# voltage_multiplier_v10.net
KiCad netlist of a schematic drawn in EAGLE
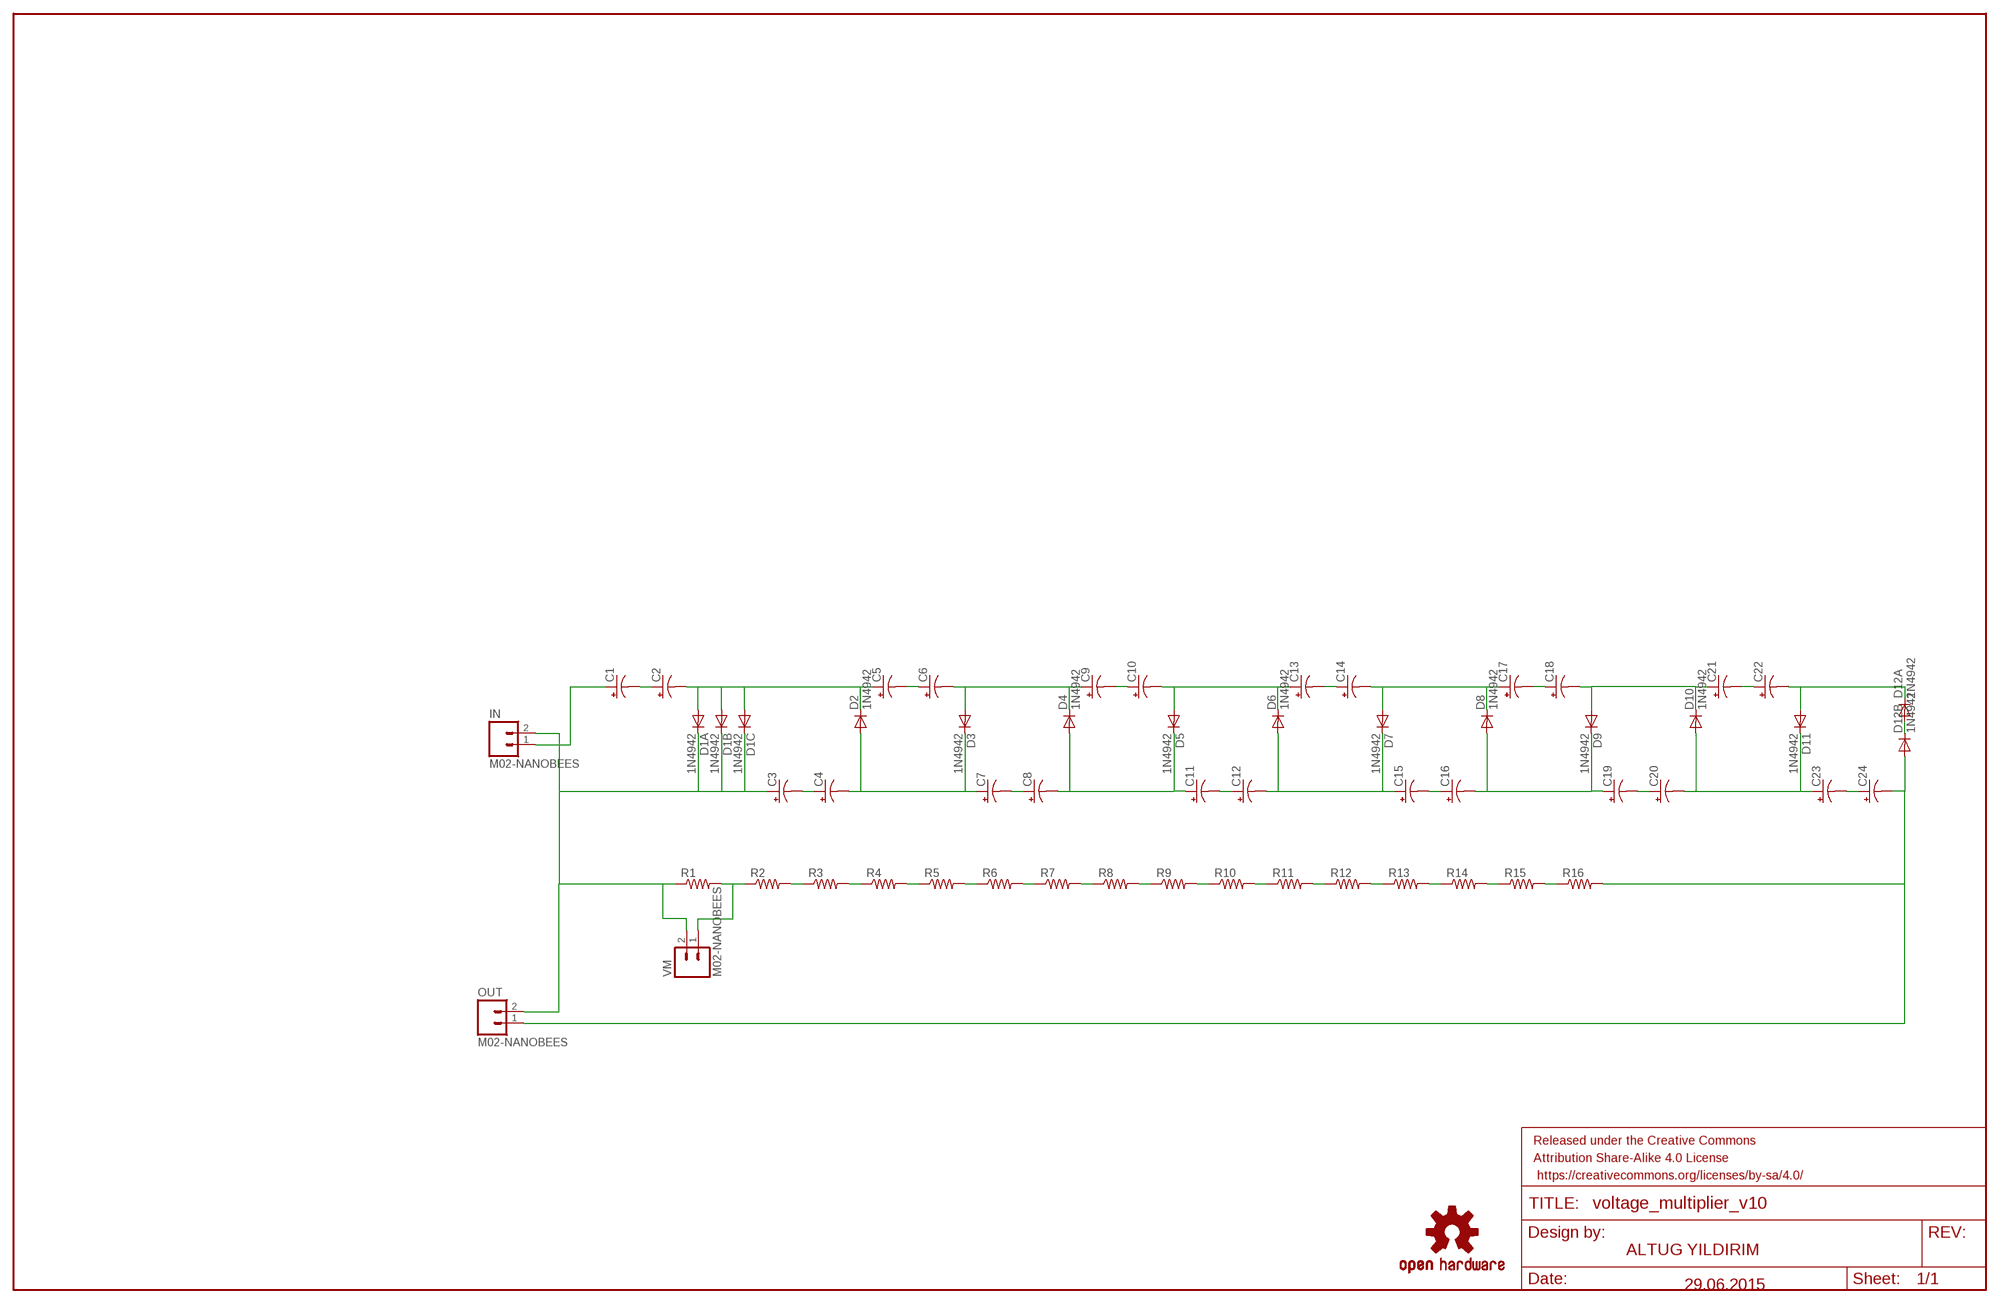
[diagram p0: schematic, sheet 1]

(export (version "E")
  (design (tool "Eeschema 10.0.6"))
  (components
    (comp (ref "C1")
      (value "CAP_POLPTH3")
      (footprint "eagle-import:CPOL-RADIAL-1000UF-63V")
      (libsource (lib "eagle-import") (part "CAP_POLPTH3"))
    )
    (comp (ref "C2")
      (value "CAP_POLPTH3")
      (footprint "eagle-import:CPOL-RADIAL-1000UF-63V")
      (libsource (lib "eagle-import") (part "CAP_POLPTH3"))
    )
    (comp (ref "C3")
      (value "CAP_POLPTH3")
      (footprint "eagle-import:CPOL-RADIAL-1000UF-63V")
      (libsource (lib "eagle-import") (part "CAP_POLPTH3"))
    )
    (comp (ref "C4")
      (value "CAP_POLPTH3")
      (footprint "eagle-import:CPOL-RADIAL-1000UF-63V")
      (libsource (lib "eagle-import") (part "CAP_POLPTH3"))
    )
    (comp (ref "C5")
      (value "CAP_POLPTH3")
      (footprint "eagle-import:CPOL-RADIAL-1000UF-63V")
      (libsource (lib "eagle-import") (part "CAP_POLPTH3"))
    )
    (comp (ref "C6")
      (value "CAP_POLPTH3")
      (footprint "eagle-import:CPOL-RADIAL-1000UF-63V")
      (libsource (lib "eagle-import") (part "CAP_POLPTH3"))
    )
    (comp (ref "C7")
      (value "CAP_POLPTH3")
      (footprint "eagle-import:CPOL-RADIAL-1000UF-63V")
      (libsource (lib "eagle-import") (part "CAP_POLPTH3"))
    )
    (comp (ref "C8")
      (value "CAP_POLPTH3")
      (footprint "eagle-import:CPOL-RADIAL-1000UF-63V")
      (libsource (lib "eagle-import") (part "CAP_POLPTH3"))
    )
    (comp (ref "C9")
      (value "CAP_POLPTH3")
      (footprint "eagle-import:CPOL-RADIAL-1000UF-63V")
      (libsource (lib "eagle-import") (part "CAP_POLPTH3"))
    )
    (comp (ref "C10")
      (value "CAP_POLPTH3")
      (footprint "eagle-import:CPOL-RADIAL-1000UF-63V")
      (libsource (lib "eagle-import") (part "CAP_POLPTH3"))
    )
    (comp (ref "C11")
      (value "CAP_POLPTH3")
      (footprint "eagle-import:CPOL-RADIAL-1000UF-63V")
      (libsource (lib "eagle-import") (part "CAP_POLPTH3"))
    )
    (comp (ref "C12")
      (value "CAP_POLPTH3")
      (footprint "eagle-import:CPOL-RADIAL-1000UF-63V")
      (libsource (lib "eagle-import") (part "CAP_POLPTH3"))
    )
    (comp (ref "C13")
      (value "CAP_POLPTH3")
      (footprint "eagle-import:CPOL-RADIAL-1000UF-63V")
      (libsource (lib "eagle-import") (part "CAP_POLPTH3"))
    )
    (comp (ref "C14")
      (value "CAP_POLPTH3")
      (footprint "eagle-import:CPOL-RADIAL-1000UF-63V")
      (libsource (lib "eagle-import") (part "CAP_POLPTH3"))
    )
    (comp (ref "C15")
      (value "CAP_POLPTH3")
      (footprint "eagle-import:CPOL-RADIAL-1000UF-63V")
      (libsource (lib "eagle-import") (part "CAP_POLPTH3"))
    )
    (comp (ref "C16")
      (value "CAP_POLPTH3")
      (footprint "eagle-import:CPOL-RADIAL-1000UF-63V")
      (libsource (lib "eagle-import") (part "CAP_POLPTH3"))
    )
    (comp (ref "C17")
      (value "CAP_POLPTH3")
      (footprint "eagle-import:CPOL-RADIAL-1000UF-63V")
      (libsource (lib "eagle-import") (part "CAP_POLPTH3"))
    )
    (comp (ref "C18")
      (value "CAP_POLPTH3")
      (footprint "eagle-import:CPOL-RADIAL-1000UF-63V")
      (libsource (lib "eagle-import") (part "CAP_POLPTH3"))
    )
    (comp (ref "C19")
      (value "CAP_POLPTH3")
      (footprint "eagle-import:CPOL-RADIAL-1000UF-63V")
      (libsource (lib "eagle-import") (part "CAP_POLPTH3"))
    )
    (comp (ref "C20")
      (value "CAP_POLPTH3")
      (footprint "eagle-import:CPOL-RADIAL-1000UF-63V")
      (libsource (lib "eagle-import") (part "CAP_POLPTH3"))
    )
    (comp (ref "C21")
      (value "CAP_POLPTH3")
      (footprint "eagle-import:CPOL-RADIAL-1000UF-63V")
      (libsource (lib "eagle-import") (part "CAP_POLPTH3"))
    )
    (comp (ref "C22")
      (value "CAP_POLPTH3")
      (footprint "eagle-import:CPOL-RADIAL-1000UF-63V")
      (libsource (lib "eagle-import") (part "CAP_POLPTH3"))
    )
    (comp (ref "C23")
      (value "CAP_POLPTH3")
      (footprint "eagle-import:CPOL-RADIAL-1000UF-63V")
      (libsource (lib "eagle-import") (part "CAP_POLPTH3"))
    )
    (comp (ref "C24")
      (value "CAP_POLPTH3")
      (footprint "eagle-import:CPOL-RADIAL-1000UF-63V")
      (libsource (lib "eagle-import") (part "CAP_POLPTH3"))
    )
    (comp (ref "D1A")
      (value "1N4942")
      (footprint "eagle-import:DO41-10")
      (libsource (lib "eagle-import") (part "1N4942"))
    )
    (comp (ref "D1B")
      (value "1N4942")
      (footprint "eagle-import:DO41-10")
      (libsource (lib "eagle-import") (part "1N4942"))
    )
    (comp (ref "D1C")
      (value "1N4942")
      (footprint "eagle-import:DO41-10")
      (libsource (lib "eagle-import") (part "1N4942"))
    )
    (comp (ref "D2")
      (value "1N4942")
      (footprint "eagle-import:DO41-10")
      (libsource (lib "eagle-import") (part "1N4942"))
    )
    (comp (ref "D3")
      (value "1N4942")
      (footprint "eagle-import:DO41-10")
      (libsource (lib "eagle-import") (part "1N4942"))
    )
    (comp (ref "D4")
      (value "1N4942")
      (footprint "eagle-import:DO41-10")
      (libsource (lib "eagle-import") (part "1N4942"))
    )
    (comp (ref "D5")
      (value "1N4942")
      (footprint "eagle-import:DO41-10")
      (libsource (lib "eagle-import") (part "1N4942"))
    )
    (comp (ref "D6")
      (value "1N4942")
      (footprint "eagle-import:DO41-10")
      (libsource (lib "eagle-import") (part "1N4942"))
    )
    (comp (ref "D7")
      (value "1N4942")
      (footprint "eagle-import:DO41-10")
      (libsource (lib "eagle-import") (part "1N4942"))
    )
    (comp (ref "D8")
      (value "1N4942")
      (footprint "eagle-import:DO41-10")
      (libsource (lib "eagle-import") (part "1N4942"))
    )
    (comp (ref "D9")
      (value "1N4942")
      (footprint "eagle-import:DO41-10")
      (libsource (lib "eagle-import") (part "1N4942"))
    )
    (comp (ref "D10")
      (value "1N4942")
      (footprint "eagle-import:DO41-10")
      (libsource (lib "eagle-import") (part "1N4942"))
    )
    (comp (ref "D11")
      (value "1N4942")
      (footprint "eagle-import:DO41-10")
      (libsource (lib "eagle-import") (part "1N4942"))
    )
    (comp (ref "D12A")
      (value "1N4942")
      (footprint "eagle-import:DO41-10")
      (libsource (lib "eagle-import") (part "1N4942"))
    )
    (comp (ref "D12B")
      (value "1N4942")
      (footprint "eagle-import:DO41-10")
      (libsource (lib "eagle-import") (part "1N4942"))
    )
    (comp (ref "FRAME1")
      (value "FRAME-LEDGER")
      (footprint "eagle-import:CREATIVE_COMMONS")
      (libsource (lib "eagle-import") (part "FRAME-LEDGER"))
    )
    (comp (ref "IN")
      (value "M02-NANOBEES")
      (footprint "eagle-import:M02-NANOBEES")
      (libsource (lib "eagle-import") (part "M02-NANOBEES"))
    )
    (comp (ref "LOGO1")
      (value "OSHW-LOGOM")
      (footprint "eagle-import:OSHW-LOGO-M")
      (libsource (lib "eagle-import") (part "OSHW-LOGOM"))
    )
    (comp (ref "OUT")
      (value "M02-NANOBEES")
      (footprint "eagle-import:M02-NANOBEES")
      (libsource (lib "eagle-import") (part "M02-NANOBEES"))
    )
    (comp (ref "R1")
      (value "RESISTORPTH-1/4W")
      (footprint "eagle-import:AXIAL-0.4")
      (libsource (lib "eagle-import") (part "RESISTORPTH-1/4W"))
    )
    (comp (ref "R2")
      (value "RESISTORPTH-1/4W")
      (footprint "eagle-import:AXIAL-0.4")
      (libsource (lib "eagle-import") (part "RESISTORPTH-1/4W"))
    )
    (comp (ref "R3")
      (value "RESISTORPTH-1/4W")
      (footprint "eagle-import:AXIAL-0.4")
      (libsource (lib "eagle-import") (part "RESISTORPTH-1/4W"))
    )
    (comp (ref "R4")
      (value "RESISTORPTH-1/4W")
      (footprint "eagle-import:AXIAL-0.4")
      (libsource (lib "eagle-import") (part "RESISTORPTH-1/4W"))
    )
    (comp (ref "R5")
      (value "RESISTORPTH-1/4W")
      (footprint "eagle-import:AXIAL-0.4")
      (libsource (lib "eagle-import") (part "RESISTORPTH-1/4W"))
    )
    (comp (ref "R6")
      (value "RESISTORPTH-1/4W")
      (footprint "eagle-import:AXIAL-0.4")
      (libsource (lib "eagle-import") (part "RESISTORPTH-1/4W"))
    )
    (comp (ref "R7")
      (value "RESISTORPTH-1/4W")
      (footprint "eagle-import:AXIAL-0.4")
      (libsource (lib "eagle-import") (part "RESISTORPTH-1/4W"))
    )
    (comp (ref "R8")
      (value "RESISTORPTH-1/4W")
      (footprint "eagle-import:AXIAL-0.4")
      (libsource (lib "eagle-import") (part "RESISTORPTH-1/4W"))
    )
    (comp (ref "R9")
      (value "RESISTORPTH-1/4W")
      (footprint "eagle-import:AXIAL-0.4")
      (libsource (lib "eagle-import") (part "RESISTORPTH-1/4W"))
    )
    (comp (ref "R10")
      (value "RESISTORPTH-1/4W")
      (footprint "eagle-import:AXIAL-0.4")
      (libsource (lib "eagle-import") (part "RESISTORPTH-1/4W"))
    )
    (comp (ref "R11")
      (value "RESISTORPTH-1/4W")
      (footprint "eagle-import:AXIAL-0.4")
      (libsource (lib "eagle-import") (part "RESISTORPTH-1/4W"))
    )
    (comp (ref "R12")
      (value "RESISTORPTH-1/4W")
      (footprint "eagle-import:AXIAL-0.4")
      (libsource (lib "eagle-import") (part "RESISTORPTH-1/4W"))
    )
    (comp (ref "R13")
      (value "RESISTORPTH-1/4W")
      (footprint "eagle-import:AXIAL-0.4")
      (libsource (lib "eagle-import") (part "RESISTORPTH-1/4W"))
    )
    (comp (ref "R14")
      (value "RESISTORPTH-1/4W")
      (footprint "eagle-import:AXIAL-0.4")
      (libsource (lib "eagle-import") (part "RESISTORPTH-1/4W"))
    )
    (comp (ref "R15")
      (value "RESISTORPTH-1/4W")
      (footprint "eagle-import:AXIAL-0.4")
      (libsource (lib "eagle-import") (part "RESISTORPTH-1/4W"))
    )
    (comp (ref "R16")
      (value "RESISTORPTH-1/4W")
      (footprint "eagle-import:AXIAL-0.4")
      (libsource (lib "eagle-import") (part "RESISTORPTH-1/4W"))
    )
    (comp (ref "VM")
      (value "M02-NANOBEES")
      (footprint "eagle-import:M02-NANOBEES")
      (libsource (lib "eagle-import") (part "M02-NANOBEES"))
    )
  )
  (nets
    (net (code "1") (name "Net-(C1-+)") (class "Default")
      (node (ref "C1") (pin "1") (pinfunction "+_1") (pintype "passive"))
      (node (ref "IN") (pin "1") (pinfunction "1_1") (pintype "passive"))
    )
    (net (code "2") (name "Net-(C1--)") (class "Default")
      (node (ref "C1") (pin "2") (pinfunction "-_2") (pintype "passive"))
      (node (ref "C2") (pin "1") (pinfunction "+_1") (pintype "passive"))
    )
    (net (code "3") (name "Net-(C2--)") (class "Default")
      (node (ref "C2") (pin "2") (pinfunction "-_2") (pintype "passive"))
      (node (ref "C5") (pin "1") (pinfunction "+_1") (pintype "passive"))
      (node (ref "D1A") (pin "A") (pinfunction "A_A") (pintype "passive"))
      (node (ref "D1B") (pin "A") (pinfunction "A_A") (pintype "passive"))
      (node (ref "D1C") (pin "A") (pinfunction "A_A") (pintype "passive"))
      (node (ref "D2") (pin "C") (pinfunction "C_C") (pintype "passive"))
    )
    (net (code "4") (name "Net-(C3-+)") (class "Default")
      (node (ref "C3") (pin "1") (pinfunction "+_1") (pintype "passive"))
      (node (ref "D1A") (pin "C") (pinfunction "C_C") (pintype "passive"))
      (node (ref "D1B") (pin "C") (pinfunction "C_C") (pintype "passive"))
      (node (ref "D1C") (pin "C") (pinfunction "C_C") (pintype "passive"))
      (node (ref "IN") (pin "2") (pinfunction "2_2") (pintype "passive"))
      (node (ref "OUT") (pin "2") (pinfunction "2_2") (pintype "passive"))
      (node (ref "R1") (pin "P$1") (pinfunction "1_P$1") (pintype "passive"))
      (node (ref "VM") (pin "2") (pinfunction "2_2") (pintype "passive"))
    )
    (net (code "5") (name "Net-(C3--)") (class "Default")
      (node (ref "C3") (pin "2") (pinfunction "-_2") (pintype "passive"))
      (node (ref "C4") (pin "1") (pinfunction "+_1") (pintype "passive"))
    )
    (net (code "6") (name "Net-(C4--)") (class "Default")
      (node (ref "C4") (pin "2") (pinfunction "-_2") (pintype "passive"))
      (node (ref "C7") (pin "1") (pinfunction "+_1") (pintype "passive"))
      (node (ref "D2") (pin "A") (pinfunction "A_A") (pintype "passive"))
      (node (ref "D3") (pin "C") (pinfunction "C_C") (pintype "passive"))
    )
    (net (code "7") (name "Net-(C5--)") (class "Default")
      (node (ref "C5") (pin "2") (pinfunction "-_2") (pintype "passive"))
      (node (ref "C6") (pin "1") (pinfunction "+_1") (pintype "passive"))
    )
    (net (code "8") (name "Net-(C6--)") (class "Default")
      (node (ref "C6") (pin "2") (pinfunction "-_2") (pintype "passive"))
      (node (ref "C9") (pin "1") (pinfunction "+_1") (pintype "passive"))
      (node (ref "D3") (pin "A") (pinfunction "A_A") (pintype "passive"))
      (node (ref "D4") (pin "C") (pinfunction "C_C") (pintype "passive"))
    )
    (net (code "9") (name "Net-(C7--)") (class "Default")
      (node (ref "C7") (pin "2") (pinfunction "-_2") (pintype "passive"))
      (node (ref "C8") (pin "1") (pinfunction "+_1") (pintype "passive"))
    )
    (net (code "10") (name "Net-(C10-+)") (class "Default")
      (node (ref "C10") (pin "1") (pinfunction "+_1") (pintype "passive"))
      (node (ref "C9") (pin "2") (pinfunction "-_2") (pintype "passive"))
    )
    (net (code "11") (name "Net-(C10--)") (class "Default")
      (node (ref "C10") (pin "2") (pinfunction "-_2") (pintype "passive"))
      (node (ref "C13") (pin "1") (pinfunction "+_1") (pintype "passive"))
      (node (ref "D5") (pin "A") (pinfunction "A_A") (pintype "passive"))
      (node (ref "D6") (pin "C") (pinfunction "C_C") (pintype "passive"))
    )
    (net (code "12") (name "Net-(C11-+)") (class "Default")
      (node (ref "C11") (pin "1") (pinfunction "+_1") (pintype "passive"))
      (node (ref "C8") (pin "2") (pinfunction "-_2") (pintype "passive"))
      (node (ref "D4") (pin "A") (pinfunction "A_A") (pintype "passive"))
      (node (ref "D5") (pin "C") (pinfunction "C_C") (pintype "passive"))
    )
    (net (code "13") (name "Net-(C11--)") (class "Default")
      (node (ref "C11") (pin "2") (pinfunction "-_2") (pintype "passive"))
      (node (ref "C12") (pin "1") (pinfunction "+_1") (pintype "passive"))
    )
    (net (code "14") (name "Net-(C12--)") (class "Default")
      (node (ref "C12") (pin "2") (pinfunction "-_2") (pintype "passive"))
      (node (ref "C15") (pin "1") (pinfunction "+_1") (pintype "passive"))
      (node (ref "D6") (pin "A") (pinfunction "A_A") (pintype "passive"))
      (node (ref "D7") (pin "C") (pinfunction "C_C") (pintype "passive"))
    )
    (net (code "15") (name "Net-(C13--)") (class "Default")
      (node (ref "C13") (pin "2") (pinfunction "-_2") (pintype "passive"))
      (node (ref "C14") (pin "1") (pinfunction "+_1") (pintype "passive"))
    )
    (net (code "16") (name "Net-(C14--)") (class "Default")
      (node (ref "C14") (pin "2") (pinfunction "-_2") (pintype "passive"))
      (node (ref "C17") (pin "1") (pinfunction "+_1") (pintype "passive"))
      (node (ref "D7") (pin "A") (pinfunction "A_A") (pintype "passive"))
      (node (ref "D8") (pin "C") (pinfunction "C_C") (pintype "passive"))
    )
    (net (code "17") (name "Net-(C15--)") (class "Default")
      (node (ref "C15") (pin "2") (pinfunction "-_2") (pintype "passive"))
      (node (ref "C16") (pin "1") (pinfunction "+_1") (pintype "passive"))
    )
    (net (code "18") (name "Net-(C16--)") (class "Default")
      (node (ref "C16") (pin "2") (pinfunction "-_2") (pintype "passive"))
      (node (ref "C19") (pin "1") (pinfunction "+_1") (pintype "passive"))
      (node (ref "D8") (pin "A") (pinfunction "A_A") (pintype "passive"))
      (node (ref "D9") (pin "C") (pinfunction "C_C") (pintype "passive"))
    )
    (net (code "19") (name "Net-(C17--)") (class "Default")
      (node (ref "C17") (pin "2") (pinfunction "-_2") (pintype "passive"))
      (node (ref "C18") (pin "1") (pinfunction "+_1") (pintype "passive"))
    )
    (net (code "20") (name "Net-(C18--)") (class "Default")
      (node (ref "C18") (pin "2") (pinfunction "-_2") (pintype "passive"))
      (node (ref "C21") (pin "1") (pinfunction "+_1") (pintype "passive"))
      (node (ref "D10") (pin "C") (pinfunction "C_C") (pintype "passive"))
      (node (ref "D9") (pin "A") (pinfunction "A_A") (pintype "passive"))
    )
    (net (code "21") (name "Net-(C19--)") (class "Default")
      (node (ref "C19") (pin "2") (pinfunction "-_2") (pintype "passive"))
      (node (ref "C20") (pin "1") (pinfunction "+_1") (pintype "passive"))
    )
    (net (code "22") (name "Net-(C20--)") (class "Default")
      (node (ref "C20") (pin "2") (pinfunction "-_2") (pintype "passive"))
      (node (ref "C23") (pin "1") (pinfunction "+_1") (pintype "passive"))
      (node (ref "D10") (pin "A") (pinfunction "A_A") (pintype "passive"))
      (node (ref "D11") (pin "C") (pinfunction "C_C") (pintype "passive"))
    )
    (net (code "23") (name "Net-(C21--)") (class "Default")
      (node (ref "C21") (pin "2") (pinfunction "-_2") (pintype "passive"))
      (node (ref "C22") (pin "1") (pinfunction "+_1") (pintype "passive"))
    )
    (net (code "24") (name "Net-(C22--)") (class "Default")
      (node (ref "C22") (pin "2") (pinfunction "-_2") (pintype "passive"))
      (node (ref "D11") (pin "A") (pinfunction "A_A") (pintype "passive"))
      (node (ref "D12A") (pin "C") (pinfunction "C_C") (pintype "passive"))
    )
    (net (code "25") (name "Net-(C23--)") (class "Default")
      (node (ref "C23") (pin "2") (pinfunction "-_2") (pintype "passive"))
      (node (ref "C24") (pin "1") (pinfunction "+_1") (pintype "passive"))
    )
    (net (code "26") (name "Net-(C24--)") (class "Default")
      (node (ref "C24") (pin "2") (pinfunction "-_2") (pintype "passive"))
      (node (ref "D12B") (pin "A") (pinfunction "A_A") (pintype "passive"))
      (node (ref "OUT") (pin "1") (pinfunction "1_1") (pintype "passive"))
      (node (ref "R16") (pin "P$2") (pinfunction "2_P$2") (pintype "passive"))
    )
    (net (code "27") (name "Net-(D12A-PadA)") (class "Default")
      (node (ref "D12A") (pin "A") (pinfunction "A_A") (pintype "passive"))
      (node (ref "D12B") (pin "C") (pinfunction "C_C") (pintype "passive"))
    )
    (net (code "28") (name "Net-(R1-2)") (class "Default")
      (node (ref "R1") (pin "P$2") (pinfunction "2_P$2") (pintype "passive"))
      (node (ref "R2") (pin "P$1") (pinfunction "1_P$1") (pintype "passive"))
      (node (ref "VM") (pin "1") (pinfunction "1_1") (pintype "passive"))
    )
    (net (code "29") (name "Net-(R2-2)") (class "Default")
      (node (ref "R2") (pin "P$2") (pinfunction "2_P$2") (pintype "passive"))
      (node (ref "R3") (pin "P$1") (pinfunction "1_P$1") (pintype "passive"))
    )
    (net (code "30") (name "Net-(R3-2)") (class "Default")
      (node (ref "R3") (pin "P$2") (pinfunction "2_P$2") (pintype "passive"))
      (node (ref "R4") (pin "P$1") (pinfunction "1_P$1") (pintype "passive"))
    )
    (net (code "31") (name "Net-(R4-2)") (class "Default")
      (node (ref "R4") (pin "P$2") (pinfunction "2_P$2") (pintype "passive"))
      (node (ref "R5") (pin "P$1") (pinfunction "1_P$1") (pintype "passive"))
    )
    (net (code "32") (name "Net-(R5-2)") (class "Default")
      (node (ref "R5") (pin "P$2") (pinfunction "2_P$2") (pintype "passive"))
      (node (ref "R6") (pin "P$1") (pinfunction "1_P$1") (pintype "passive"))
    )
    (net (code "33") (name "Net-(R6-2)") (class "Default")
      (node (ref "R6") (pin "P$2") (pinfunction "2_P$2") (pintype "passive"))
      (node (ref "R7") (pin "P$1") (pinfunction "1_P$1") (pintype "passive"))
    )
    (net (code "34") (name "Net-(R7-2)") (class "Default")
      (node (ref "R7") (pin "P$2") (pinfunction "2_P$2") (pintype "passive"))
      (node (ref "R8") (pin "P$1") (pinfunction "1_P$1") (pintype "passive"))
    )
    (net (code "35") (name "Net-(R8-2)") (class "Default")
      (node (ref "R8") (pin "P$2") (pinfunction "2_P$2") (pintype "passive"))
      (node (ref "R9") (pin "P$1") (pinfunction "1_P$1") (pintype "passive"))
    )
    (net (code "36") (name "Net-(R10-1)") (class "Default")
      (node (ref "R10") (pin "P$1") (pinfunction "1_P$1") (pintype "passive"))
      (node (ref "R9") (pin "P$2") (pinfunction "2_P$2") (pintype "passive"))
    )
    (net (code "37") (name "Net-(R10-2)") (class "Default")
      (node (ref "R10") (pin "P$2") (pinfunction "2_P$2") (pintype "passive"))
      (node (ref "R11") (pin "P$1") (pinfunction "1_P$1") (pintype "passive"))
    )
    (net (code "38") (name "Net-(R11-2)") (class "Default")
      (node (ref "R11") (pin "P$2") (pinfunction "2_P$2") (pintype "passive"))
      (node (ref "R12") (pin "P$1") (pinfunction "1_P$1") (pintype "passive"))
    )
    (net (code "39") (name "Net-(R12-2)") (class "Default")
      (node (ref "R12") (pin "P$2") (pinfunction "2_P$2") (pintype "passive"))
      (node (ref "R13") (pin "P$1") (pinfunction "1_P$1") (pintype "passive"))
    )
    (net (code "40") (name "Net-(R13-2)") (class "Default")
      (node (ref "R13") (pin "P$2") (pinfunction "2_P$2") (pintype "passive"))
      (node (ref "R14") (pin "P$1") (pinfunction "1_P$1") (pintype "passive"))
    )
    (net (code "41") (name "Net-(R14-2)") (class "Default")
      (node (ref "R14") (pin "P$2") (pinfunction "2_P$2") (pintype "passive"))
      (node (ref "R15") (pin "P$1") (pinfunction "1_P$1") (pintype "passive"))
    )
    (net (code "42") (name "Net-(R15-2)") (class "Default")
      (node (ref "R15") (pin "P$2") (pinfunction "2_P$2") (pintype "passive"))
      (node (ref "R16") (pin "P$1") (pinfunction "1_P$1") (pintype "passive"))
    )
  )
)
